# Board_v_03b.net
KiCad netlist of a schematic drawn in EAGLE
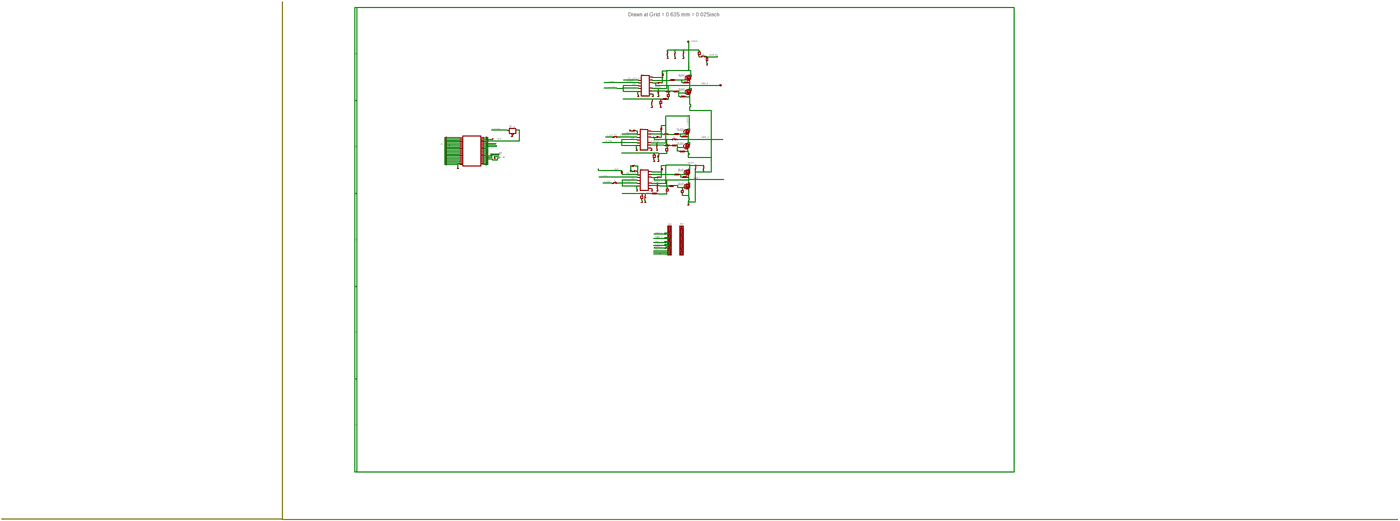
[diagram p0: schematic, sheet 1, overview]
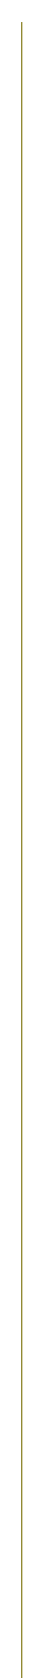
[diagram p1: schematic, sheet 1, part 1 of 7]
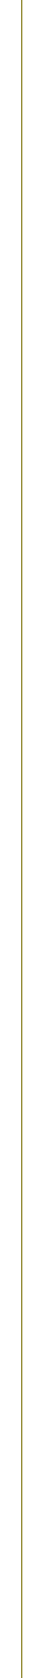
[diagram p2: schematic, sheet 1, part 2 of 7]
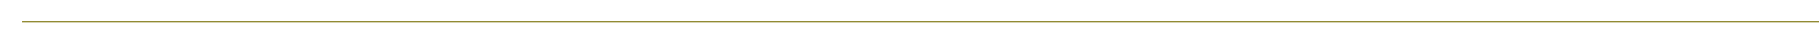
[diagram p3: schematic, sheet 1, part 3 of 7]
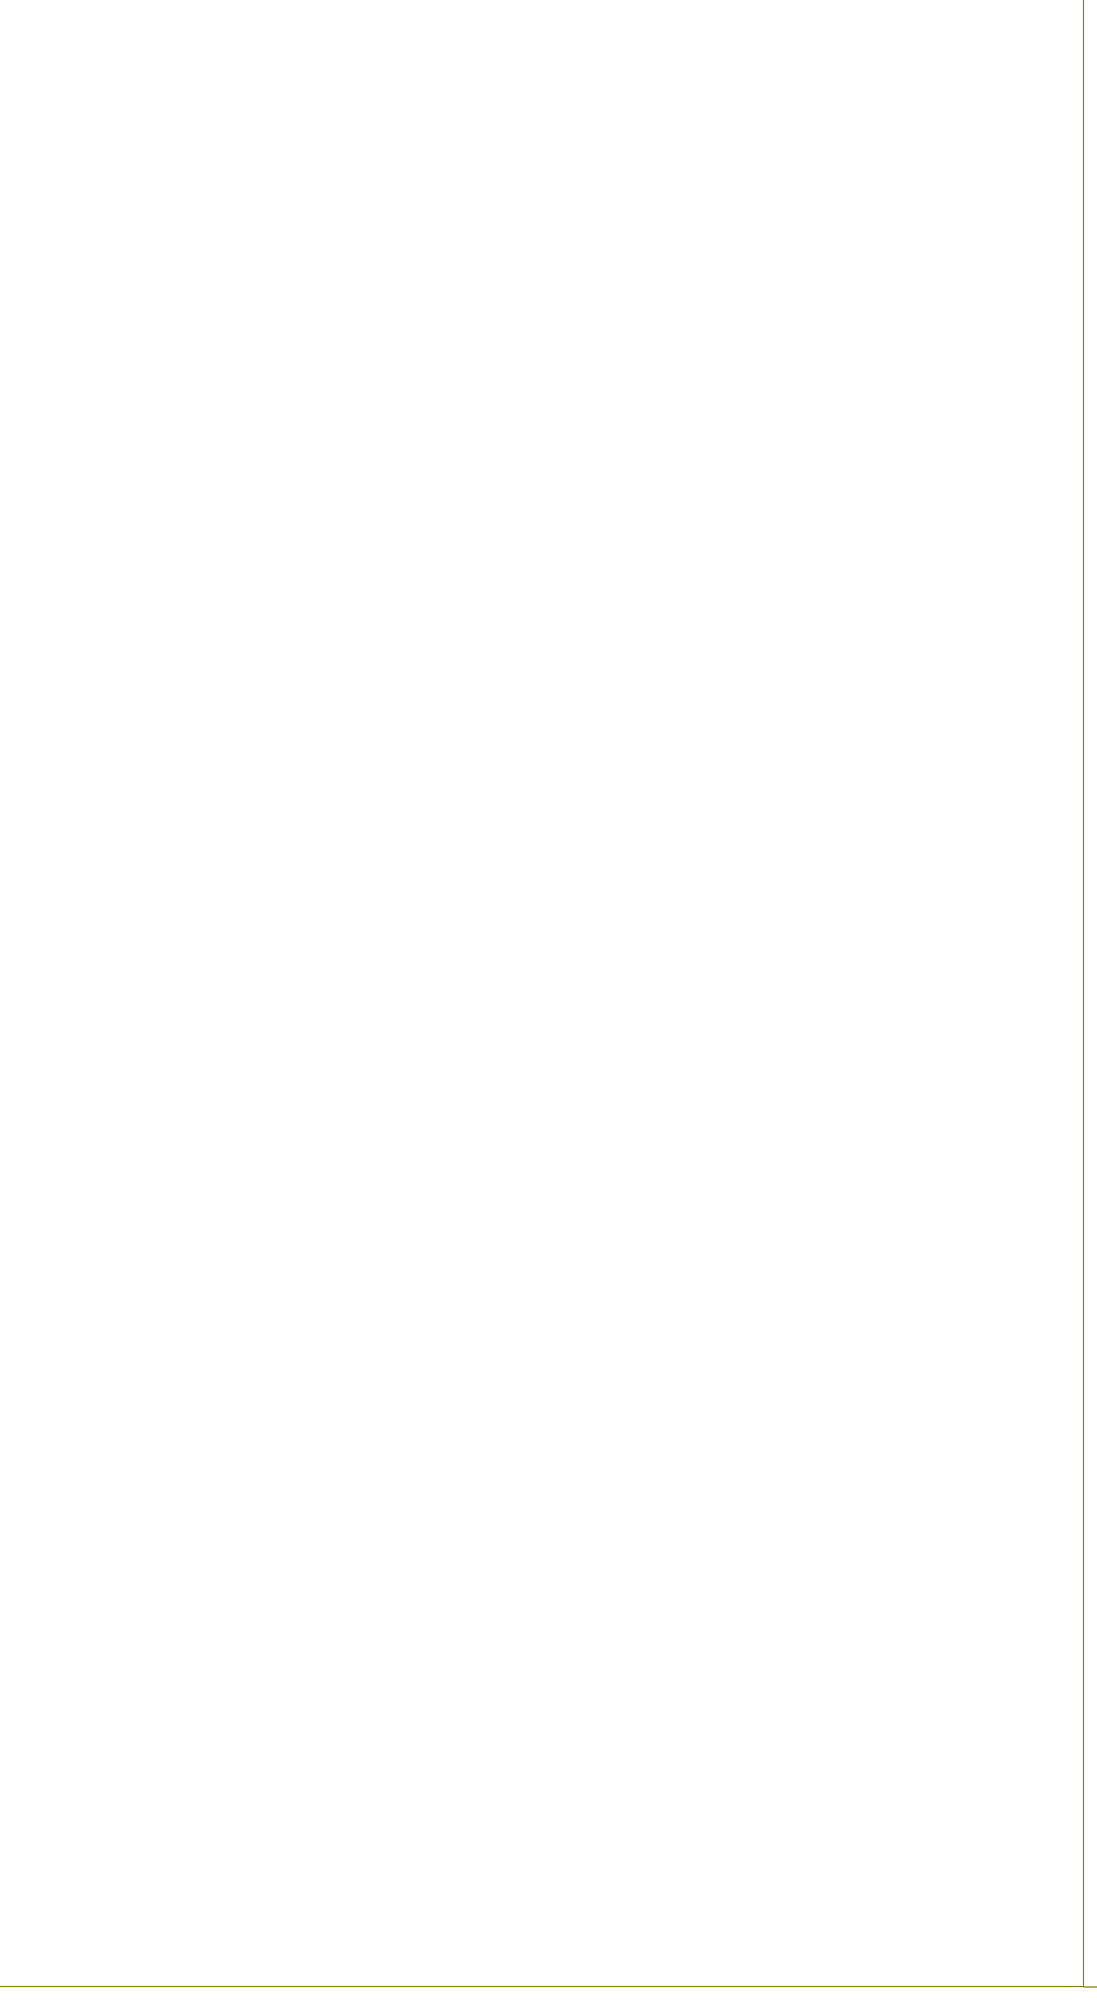
[diagram p4: schematic, sheet 1, part 4 of 7]
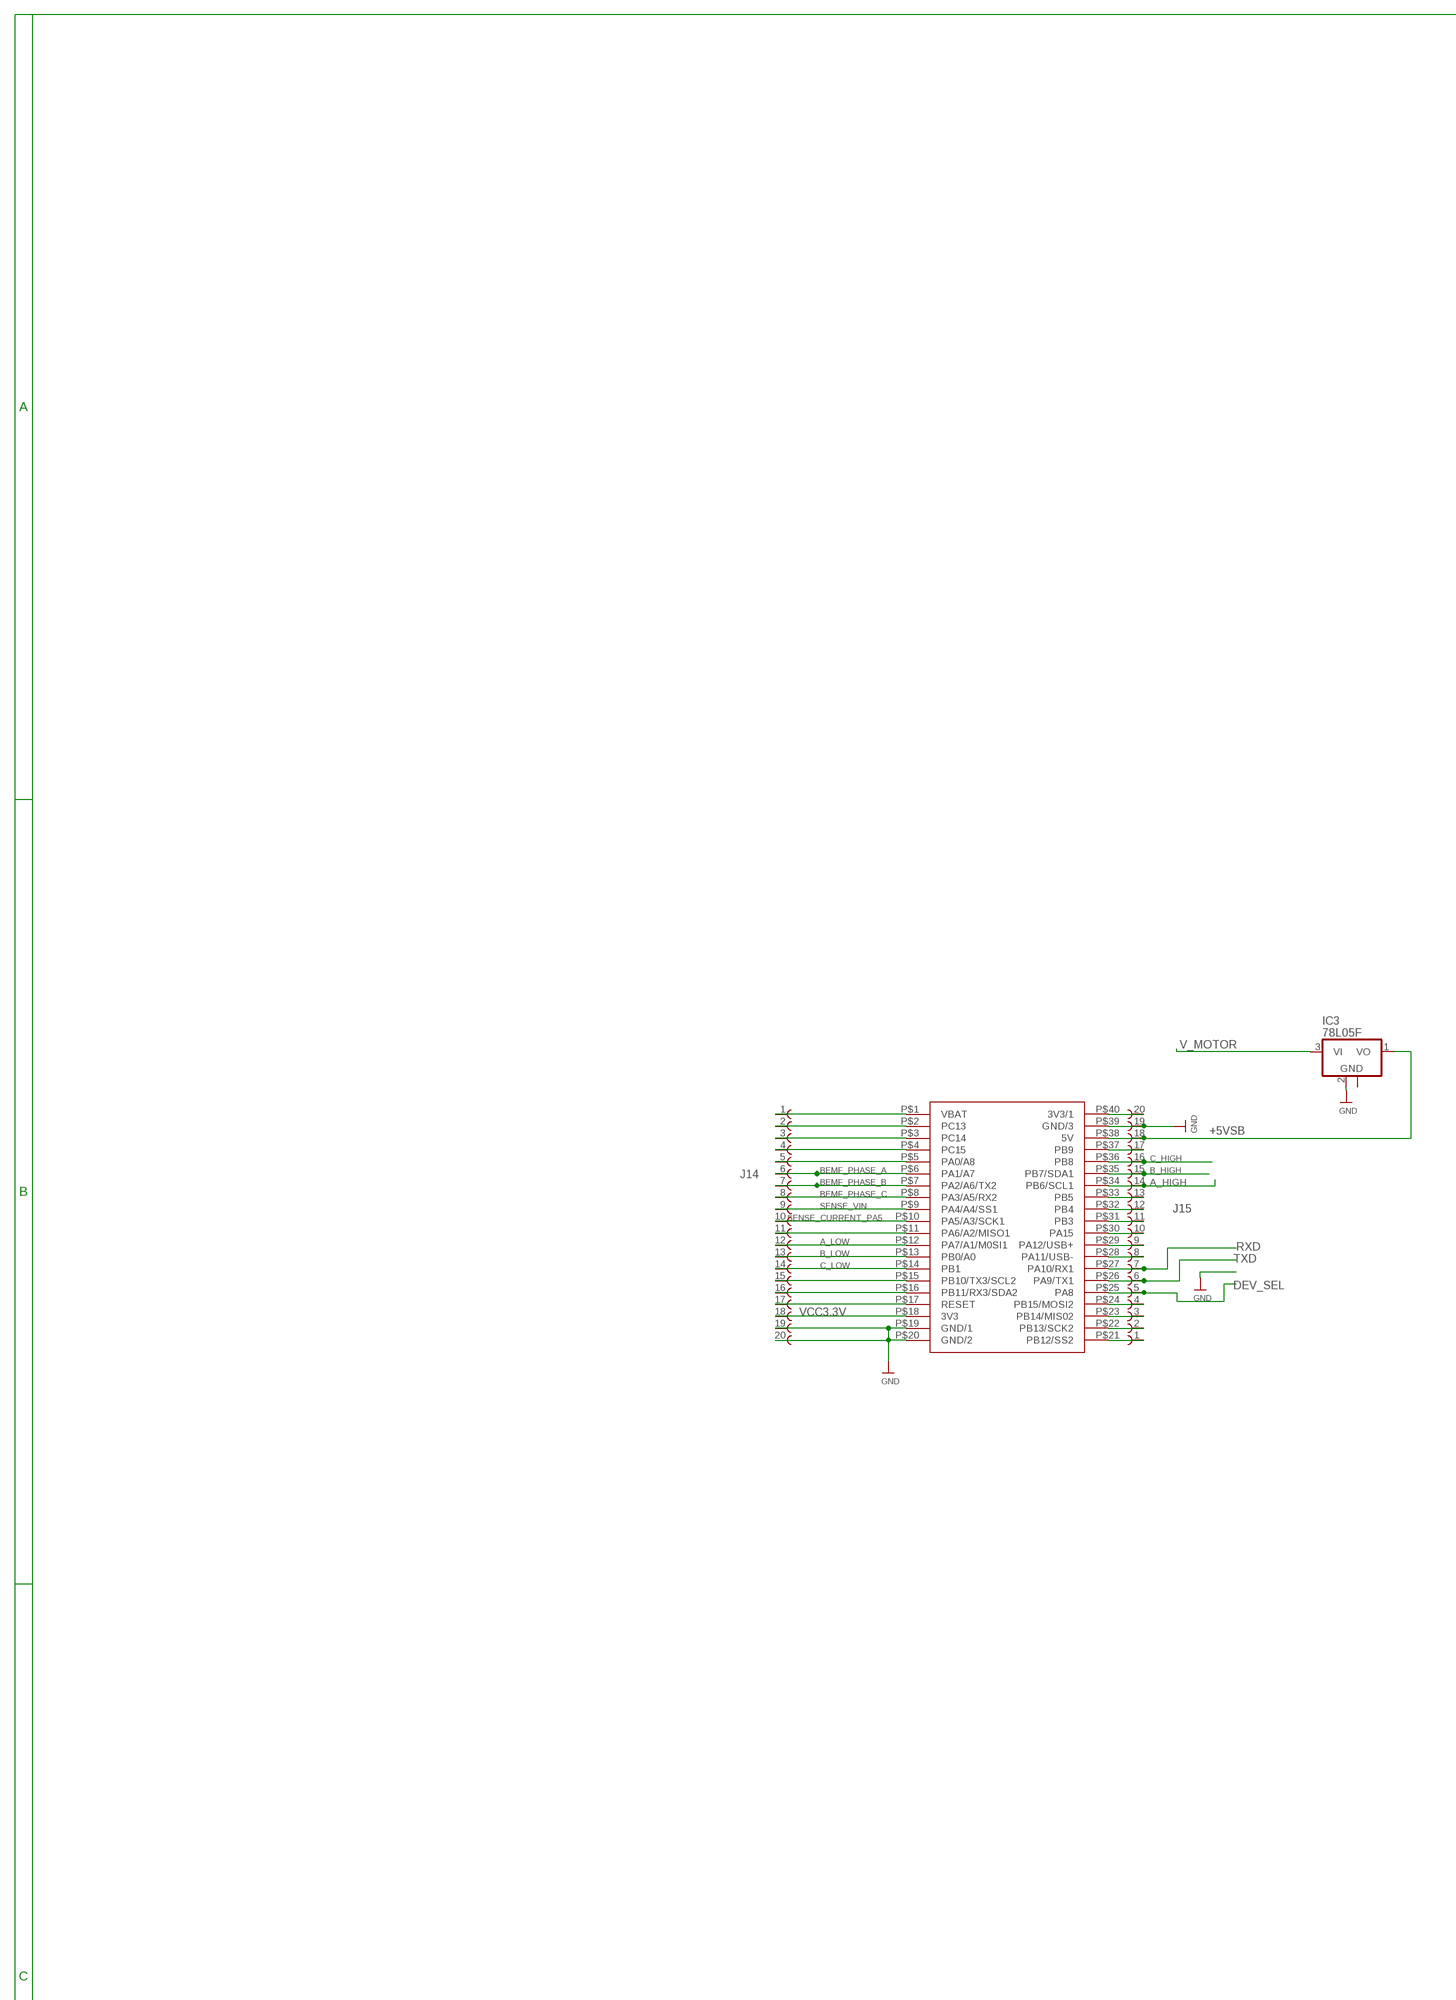
[diagram p5: schematic, sheet 1, part 5 of 7]
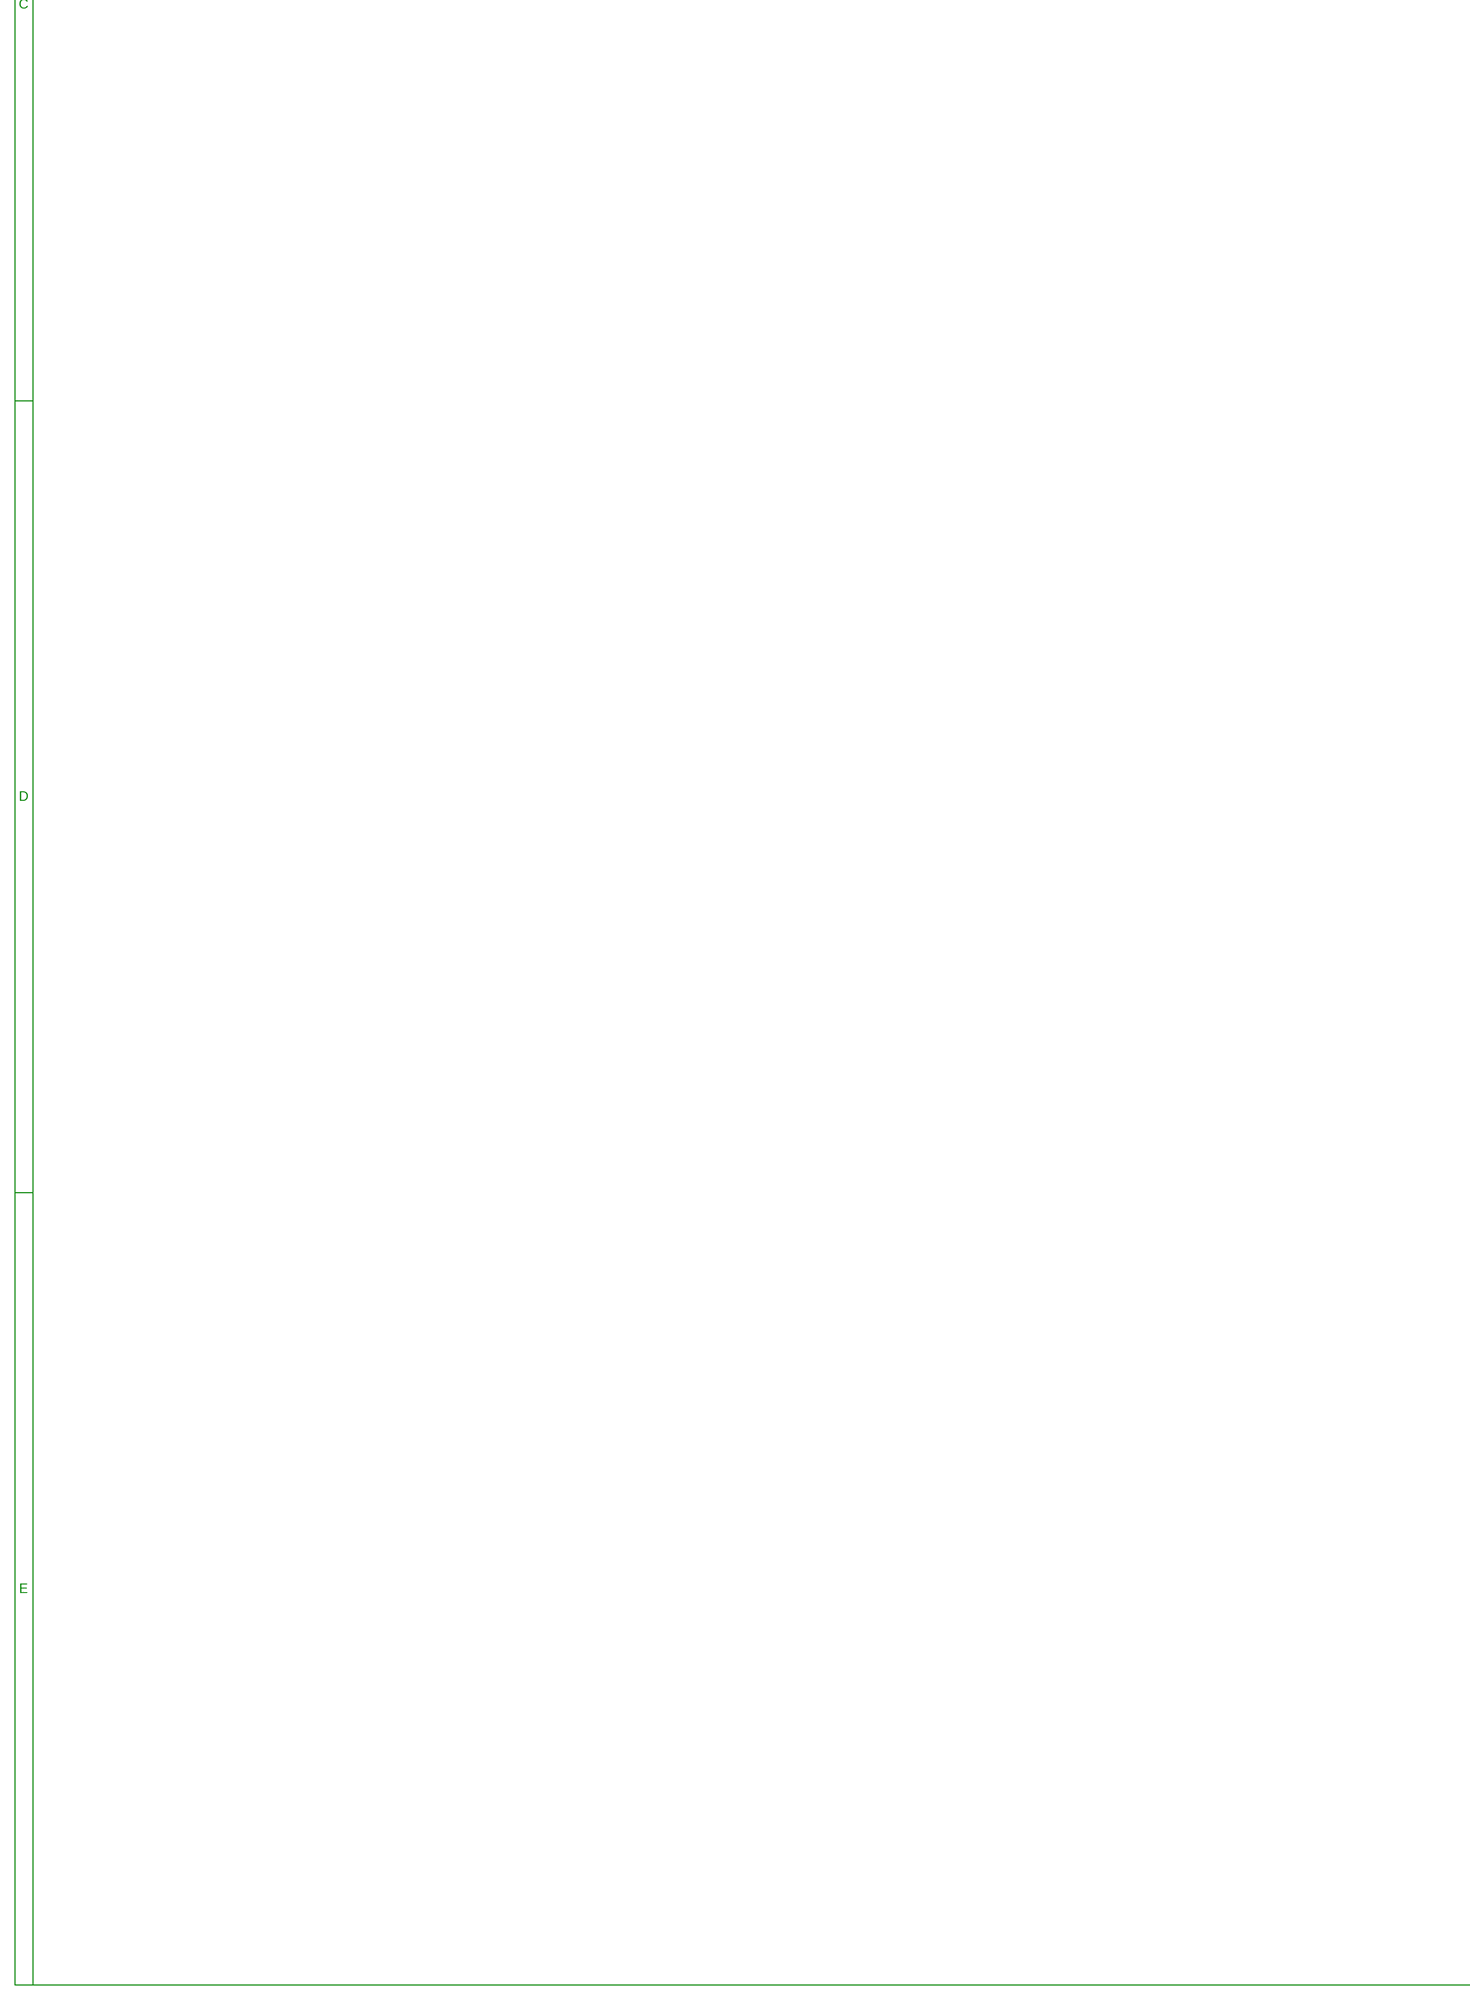
[diagram p6: schematic, sheet 1, part 6 of 7]
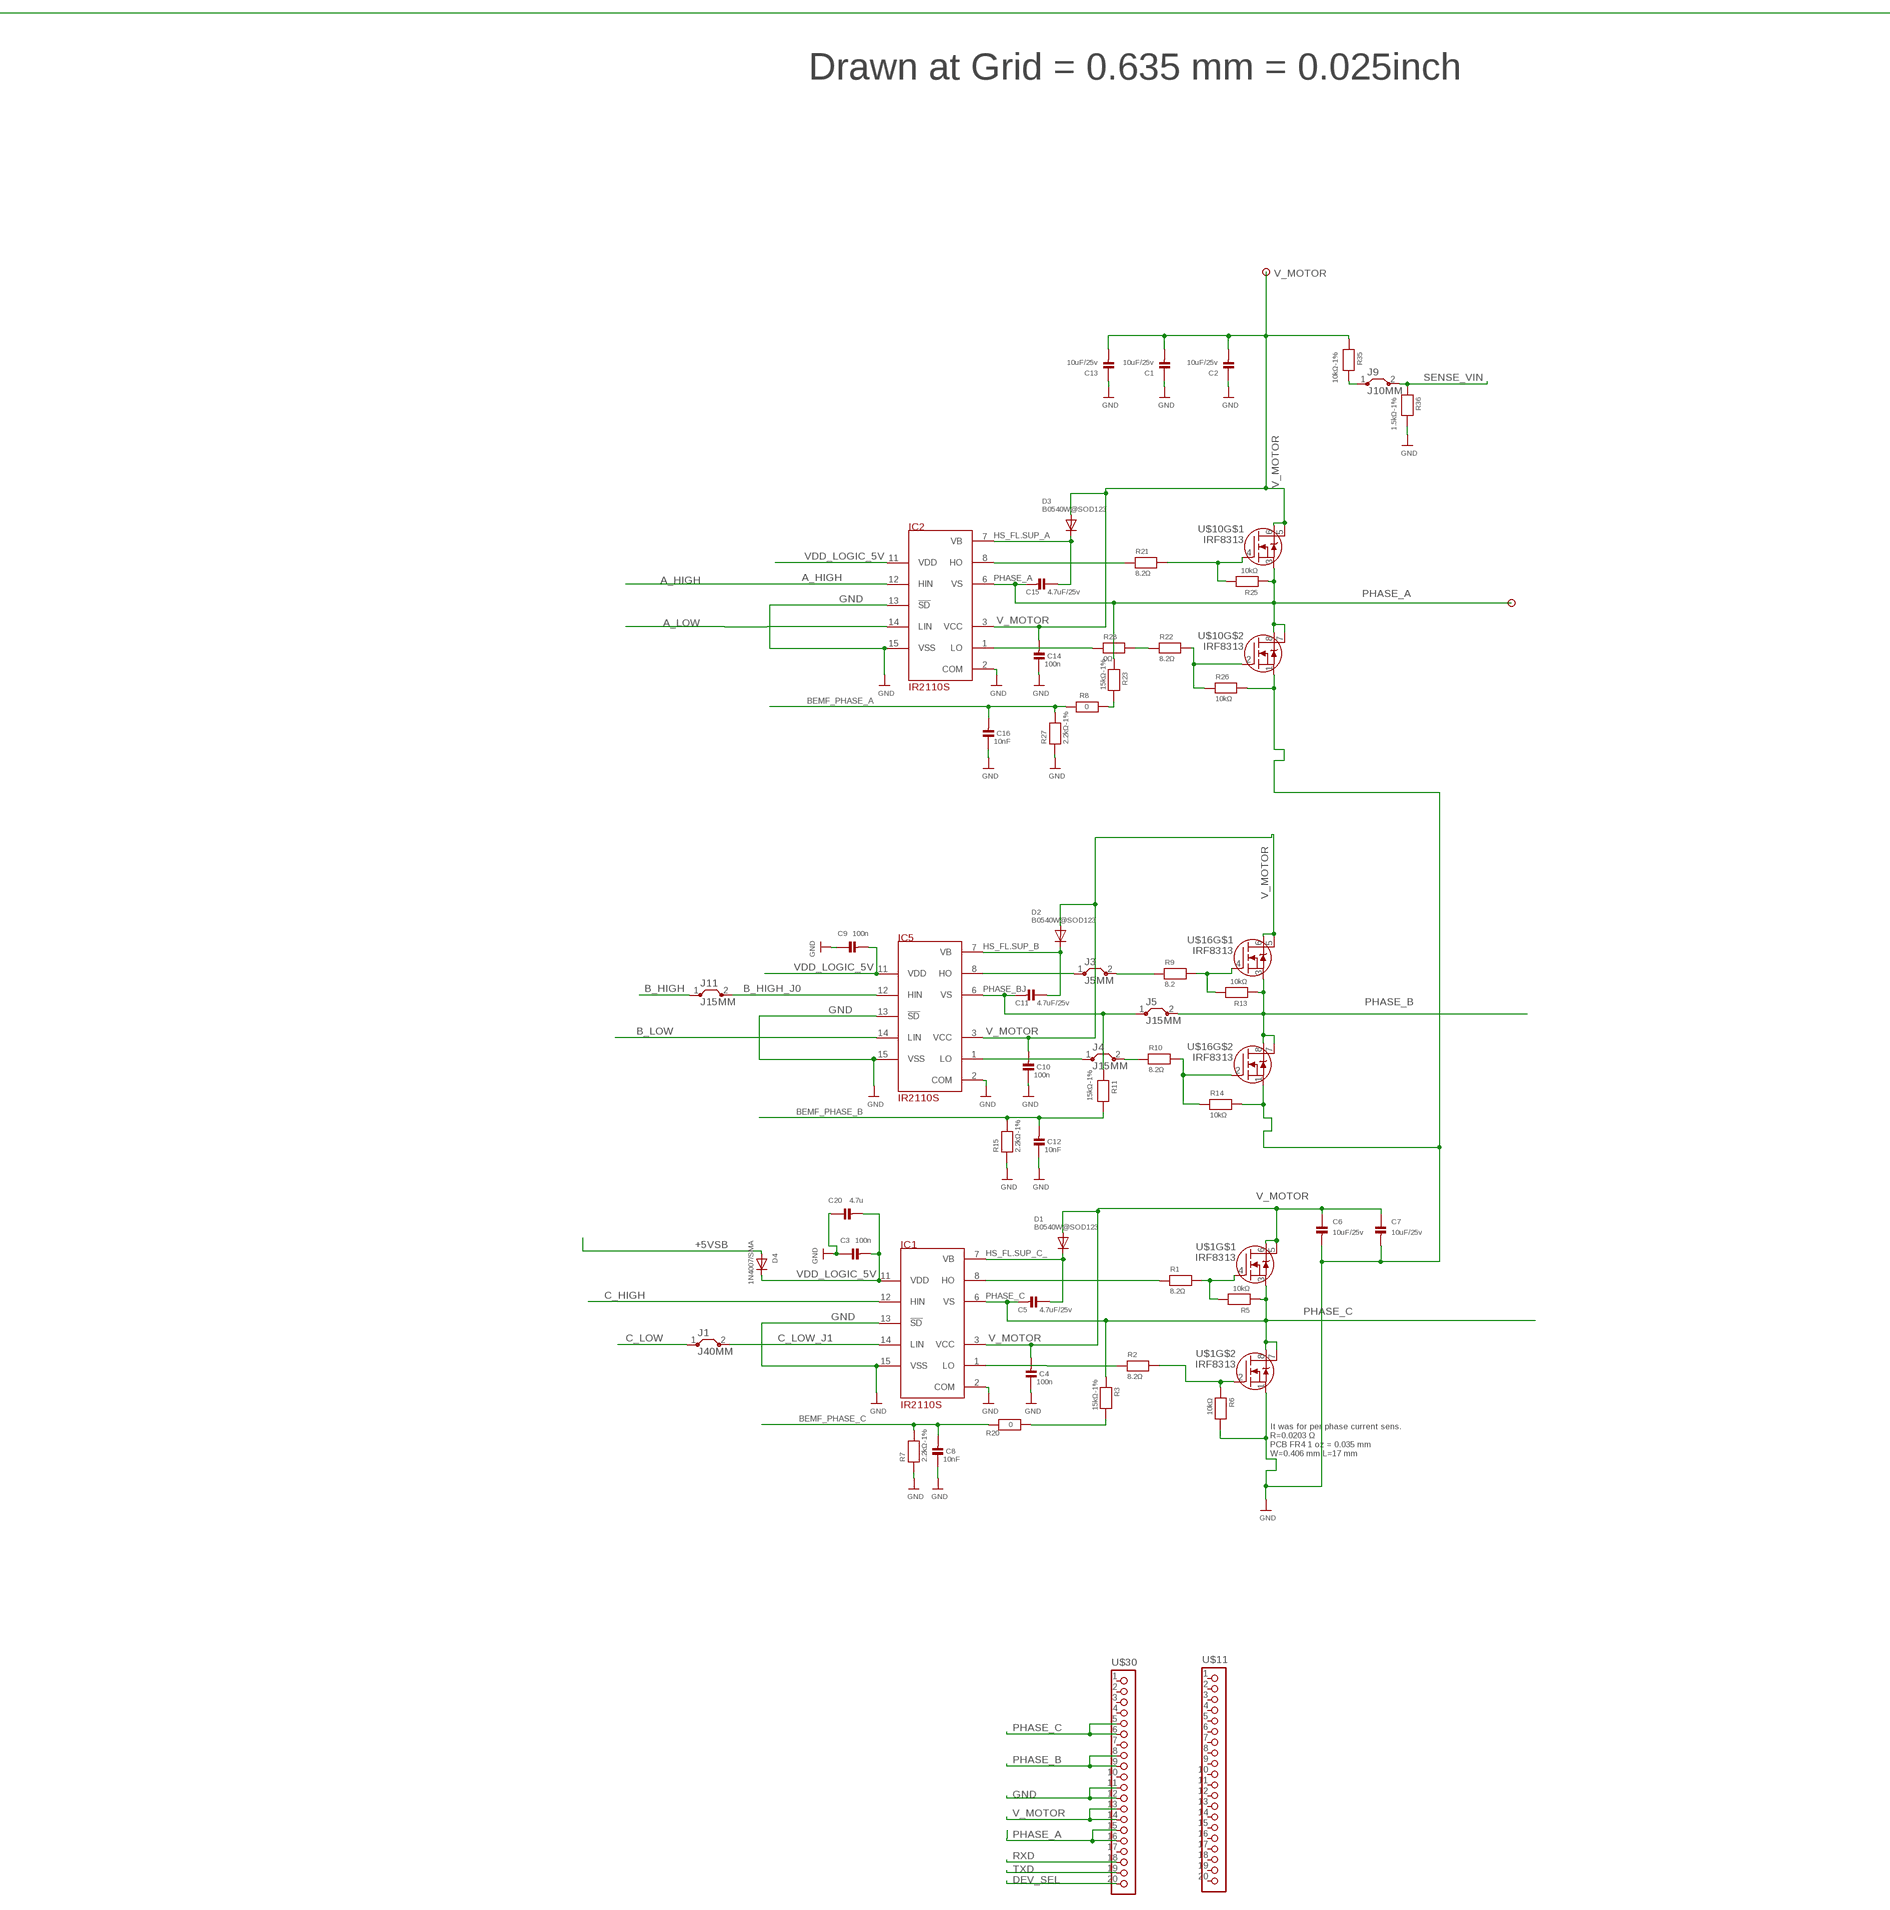
[diagram p7: schematic, sheet 1, part 7 of 7]

(export (version "E")
  (design (tool "Eeschema 10.0.6"))
  (components
    (comp (ref "C1")
      (value "10uF/25v")
      (footprint "eagle-import:_0805MP")
      (libsource (lib "eagle-import") (part "CAP_CERAMIC_0805MP"))
    )
    (comp (ref "C2")
      (value "10uF/25v")
      (footprint "eagle-import:_0805MP")
      (libsource (lib "eagle-import") (part "CAP_CERAMIC_0805MP"))
    )
    (comp (ref "C3")
      (value "100n")
      (footprint "eagle-import:_0805MP")
      (libsource (lib "eagle-import") (part "CAP_CERAMIC_0805MP"))
    )
    (comp (ref "C4")
      (value "100n")
      (footprint "eagle-import:_0603MP")
      (libsource (lib "eagle-import") (part "CAP_CERAMIC_0603MP"))
    )
    (comp (ref "C5")
      (value "4.7uF/25v")
      (footprint "eagle-import:_0805MP")
      (libsource (lib "eagle-import") (part "CAP_CERAMIC_0805MP"))
    )
    (comp (ref "C6")
      (value "10uF/25v")
      (footprint "eagle-import:_0805MP")
      (libsource (lib "eagle-import") (part "CAP_CERAMIC_0805MP"))
    )
    (comp (ref "C7")
      (value "10uF/25v")
      (footprint "eagle-import:_0805MP")
      (libsource (lib "eagle-import") (part "CAP_CERAMIC_0805MP"))
    )
    (comp (ref "C8")
      (value "10nF")
      (footprint "eagle-import:_0805MP")
      (libsource (lib "eagle-import") (part "CAP_CERAMIC_0805MP"))
    )
    (comp (ref "C9")
      (value "100n")
      (footprint "eagle-import:_0603MP")
      (libsource (lib "eagle-import") (part "CAP_CERAMIC_0603MP"))
    )
    (comp (ref "C10")
      (value "100n")
      (footprint "eagle-import:_0603MP")
      (libsource (lib "eagle-import") (part "CAP_CERAMIC_0603MP"))
    )
    (comp (ref "C11")
      (value "4.7uF/25v")
      (footprint "eagle-import:_0805MP")
      (libsource (lib "eagle-import") (part "CAP_CERAMIC_0805MP"))
    )
    (comp (ref "C12")
      (value "10nF")
      (footprint "eagle-import:_0805MP")
      (libsource (lib "eagle-import") (part "CAP_CERAMIC_0805MP"))
    )
    (comp (ref "C13")
      (value "10uF/25v")
      (footprint "eagle-import:_0805MP")
      (libsource (lib "eagle-import") (part "CAP_CERAMIC_0805MP"))
    )
    (comp (ref "C14")
      (value "100n")
      (footprint "eagle-import:_0603MP")
      (libsource (lib "eagle-import") (part "CAP_CERAMIC_0603MP"))
    )
    (comp (ref "C15")
      (value "4.7uF/25v")
      (footprint "eagle-import:_0805MP")
      (libsource (lib "eagle-import") (part "CAP_CERAMIC_0805MP"))
    )
    (comp (ref "C16")
      (value "10nF")
      (footprint "eagle-import:_0805MP")
      (libsource (lib "eagle-import") (part "CAP_CERAMIC_0805MP"))
    )
    (comp (ref "C20")
      (value "4.7u")
      (footprint "eagle-import:_0805MP")
      (libsource (lib "eagle-import") (part "CAP_CERAMIC_0805MP"))
    )
    (comp (ref "D1")
      (value "B0540W@SOD123")
      (footprint "eagle-import:SOD-123")
      (libsource (lib "eagle-import") (part "DIODESOD-123"))
    )
    (comp (ref "D2")
      (value "B0540W@SOD123")
      (footprint "eagle-import:SOD-123")
      (libsource (lib "eagle-import") (part "DIODESOD-123"))
    )
    (comp (ref "D3")
      (value "B0540W@SOD123")
      (footprint "eagle-import:SOD-123")
      (libsource (lib "eagle-import") (part "DIODESOD-123"))
    )
    (comp (ref "D4")
      (value "1N4007/SMA")
      (footprint "eagle-import:SMADIODE")
      (libsource (lib "eagle-import") (part "DIODESMA"))
    )
    (comp (ref "IC1")
      (value "IR2110S")
      (footprint "eagle-import:SO-16DW")
      (libsource (lib "eagle-import") (part "IR2110S"))
    )
    (comp (ref "IC2")
      (value "IR2110S")
      (footprint "eagle-import:SO-16DW")
      (libsource (lib "eagle-import") (part "IR2110S"))
    )
    (comp (ref "IC3")
      (value "78L05F")
      (footprint "eagle-import:SOT89")
      (libsource (lib "eagle-import") (part "78LF05"))
    )
    (comp (ref "IC5")
      (value "IR2110S")
      (footprint "eagle-import:SO-16DW")
      (libsource (lib "eagle-import") (part "IR2110S"))
    )
    (comp (ref "J1")
      (value "J40MM")
      (footprint "eagle-import:J40MM")
      (libsource (lib "eagle-import") (part "J40MM"))
    )
    (comp (ref "J3")
      (value "J5MM")
      (footprint "eagle-import:05")
      (libsource (lib "eagle-import") (part "jumper_J5MM"))
    )
    (comp (ref "J4")
      (value "J15MM")
      (footprint "eagle-import:15")
      (libsource (lib "eagle-import") (part "jumper_J15MM"))
    )
    (comp (ref "J5")
      (value "J15MM")
      (footprint "eagle-import:15")
      (libsource (lib "eagle-import") (part "jumper_J15MM"))
    )
    (comp (ref "J9")
      (value "J10MM")
      (footprint "eagle-import:10")
      (libsource (lib "eagle-import") (part "jumper_J10MM"))
    )
    (comp (ref "J11")
      (value "J15MM")
      (footprint "eagle-import:15")
      (libsource (lib "eagle-import") (part "jumper_J15MM"))
    )
    (comp (ref "J14")
      (value "61002013321")
      (footprint "eagle-import:CON-20PIN-SMD-MANUALLY-BENT-FROM-NON-SMD")
      (libsource (lib "eagle-import") (part "61002013321"))
    )
    (comp (ref "J15")
      (value "61002013321")
      (footprint "eagle-import:CON-20PIN-SMD-MANUALLY-BENT-FROM-NON-SMD")
      (libsource (lib "eagle-import") (part "61002013321"))
    )
    (comp (ref "PHASE_C")
      (value "PHASE_C")
      (footprint "eagle-import:PAD")
      (libsource (lib "eagle-import") (part "PAD"))
    )
    (comp (ref "R1")
      (value "8.2Ω")
      (footprint "eagle-import:_0805MP")
      (libsource (lib "eagle-import") (part "RESISTOR_0805MP"))
    )
    (comp (ref "R2")
      (value "8.2Ω")
      (footprint "eagle-import:_0805MP")
      (libsource (lib "eagle-import") (part "RESISTOR_0805MP"))
    )
    (comp (ref "R3")
      (value "15kΩ-1%")
      (footprint "eagle-import:_0805MP")
      (libsource (lib "eagle-import") (part "RESISTOR_0805MP"))
    )
    (comp (ref "R5")
      (value "10kΩ")
      (footprint "eagle-import:_0805MP")
      (libsource (lib "eagle-import") (part "RESISTOR_0805MP"))
    )
    (comp (ref "R6")
      (value "10kΩ")
      (footprint "eagle-import:_0805MP")
      (libsource (lib "eagle-import") (part "RESISTOR_0805MP"))
    )
    (comp (ref "R7")
      (value "2.2kΩ-1%")
      (footprint "eagle-import:_0805MP")
      (libsource (lib "eagle-import") (part "RESISTOR_0805MP"))
    )
    (comp (ref "R8")
      (value "0")
      (footprint "eagle-import:_0805MP")
      (libsource (lib "eagle-import") (part "RESISTOR_0805MP"))
    )
    (comp (ref "R9")
      (value "8.2")
      (footprint "eagle-import:_0805MP")
      (libsource (lib "eagle-import") (part "RESISTOR_0805MP"))
    )
    (comp (ref "R10")
      (value "8.2Ω")
      (footprint "eagle-import:_0805MP")
      (libsource (lib "eagle-import") (part "RESISTOR_0805MP"))
    )
    (comp (ref "R11")
      (value "15kΩ-1%")
      (footprint "eagle-import:_0805MP")
      (libsource (lib "eagle-import") (part "RESISTOR_0805MP"))
    )
    (comp (ref "R13")
      (value "10kΩ")
      (footprint "eagle-import:_0805MP")
      (libsource (lib "eagle-import") (part "RESISTOR_0805MP"))
    )
    (comp (ref "R14")
      (value "10kΩ")
      (footprint "eagle-import:_0805MP")
      (libsource (lib "eagle-import") (part "RESISTOR_0805MP"))
    )
    (comp (ref "R15")
      (value "2.2kΩ-1%")
      (footprint "eagle-import:_0805MP")
      (libsource (lib "eagle-import") (part "RESISTOR_0805MP"))
    )
    (comp (ref "R20")
      (value "0")
      (footprint "eagle-import:_0805MP")
      (libsource (lib "eagle-import") (part "RESISTOR_0805MP"))
    )
    (comp (ref "R21")
      (value "8.2Ω")
      (footprint "eagle-import:_0805MP")
      (libsource (lib "eagle-import") (part "RESISTOR_0805MP"))
    )
    (comp (ref "R22")
      (value "8.2Ω")
      (footprint "eagle-import:_0805MP")
      (libsource (lib "eagle-import") (part "RESISTOR_0805MP"))
    )
    (comp (ref "R23")
      (value "15kΩ-1%")
      (footprint "eagle-import:_0805MP")
      (libsource (lib "eagle-import") (part "RESISTOR_0805MP"))
    )
    (comp (ref "R25")
      (value "10kΩ")
      (footprint "eagle-import:_0805MP")
      (libsource (lib "eagle-import") (part "RESISTOR_0805MP"))
    )
    (comp (ref "R26")
      (value "10kΩ")
      (footprint "eagle-import:_0805MP")
      (libsource (lib "eagle-import") (part "RESISTOR_0805MP"))
    )
    (comp (ref "R27")
      (value "2.2kΩ-1%")
      (footprint "eagle-import:_0805MP")
      (libsource (lib "eagle-import") (part "RESISTOR_0805MP"))
    )
    (comp (ref "R28")
      (value "0Ω")
      (footprint "eagle-import:_0805MP")
      (libsource (lib "eagle-import") (part "RESISTOR_0805MP"))
    )
    (comp (ref "R35")
      (value "10kΩ-1%")
      (footprint "eagle-import:_0805MP")
      (libsource (lib "eagle-import") (part "RESISTOR_0805MP"))
    )
    (comp (ref "R36")
      (value "1.5kΩ-1%")
      (footprint "eagle-import:_0805MP")
      (libsource (lib "eagle-import") (part "RESISTOR_0805MP"))
    )
    (comp (ref "U$1")
      (value "IRF8313")
      (footprint "eagle-import:SO08")
      (libsource (lib "eagle-import") (part "IRF8313"))
    )
    (comp (ref "U$10")
      (value "IRF8313")
      (footprint "eagle-import:SO08")
      (libsource (lib "eagle-import") (part "IRF8313"))
    )
    (comp (ref "U$11")
      (value "CON_HEADER_1X20")
      (footprint "eagle-import:M1X20_SMD_2.54MM_0.1__LONGTRACKS")
      (libsource (lib "eagle-import") (part "CON_HEADER_1X20"))
    )
    (comp (ref "U$16")
      (value "IRF8313")
      (footprint "eagle-import:SO08")
      (libsource (lib "eagle-import") (part "IRF8313"))
    )
    (comp (ref "U$30")
      (value "CON_HEADER_1X20")
      (footprint "eagle-import:M1X20_SMD_2.54MM_0.1__LONGTRACKS")
      (libsource (lib "eagle-import") (part "CON_HEADER_1X20"))
    )
    (comp (ref "U$36")
      (value "BLUEPILL")
      (footprint "eagle-import:40-DIP-BLUE-PIL")
      (libsource (lib "eagle-import") (part "BLUEPILL"))
    )
    (comp (ref "V_MOTOR")
      (value "V_MOTOR")
      (footprint "eagle-import:PAD")
      (libsource (lib "eagle-import") (part "PAD"))
    )
  )
  (nets
    (net (code "1") (name "/+5VSB") (class "Default")
      (node (ref "D4") (pin "A") (pinfunction "A_A") (pintype "passive"))
      (node (ref "IC3") (pin "1") (pinfunction "VO_1") (pintype "passive"))
      (node (ref "J15") (pin "18") (pinfunction "18_18") (pintype "passive"))
      (node (ref "U$36") (pin "P$38") (pinfunction "5V_P$38") (pintype "bidirectional"))
    )
    (net (code "2") (name "/A_HIGH") (class "Default")
      (node (ref "IC2") (pin "12") (pinfunction "HIN_12") (pintype "input"))
      (node (ref "J15") (pin "14") (pinfunction "14_14") (pintype "passive"))
      (node (ref "U$36") (pin "P$34") (pinfunction "PB6/SCL1_P$34") (pintype "bidirectional"))
    )
    (net (code "3") (name "/A_LOW") (class "Default")
      (node (ref "IC2") (pin "14") (pinfunction "LIN_14") (pintype "input"))
      (node (ref "J14") (pin "12") (pinfunction "12_12") (pintype "passive"))
      (node (ref "U$36") (pin "P$12") (pinfunction "PA7/A1/M0SI1_P$12") (pintype "bidirectional"))
    )
    (net (code "4") (name "/BEMF_PHASE_A") (class "Default")
      (node (ref "C16") (pin "2") (pinfunction "P$2_2") (pintype "passive"))
      (node (ref "J14") (pin "6") (pinfunction "6_6") (pintype "passive"))
      (node (ref "R27") (pin "2") (pinfunction "2_2") (pintype "passive"))
      (node (ref "R8") (pin "1") (pinfunction "1_1") (pintype "passive"))
      (node (ref "U$36") (pin "P$6") (pinfunction "PA1/A7_P$6") (pintype "bidirectional"))
    )
    (net (code "5") (name "/BEMF_PHASE_B") (class "Default")
      (node (ref "C12") (pin "2") (pinfunction "P$2_2") (pintype "passive"))
      (node (ref "J14") (pin "7") (pinfunction "7_7") (pintype "passive"))
      (node (ref "R11") (pin "2") (pinfunction "2_2") (pintype "passive"))
      (node (ref "R15") (pin "2") (pinfunction "2_2") (pintype "passive"))
      (node (ref "U$36") (pin "P$7") (pinfunction "PA2/A6/TX2_P$7") (pintype "bidirectional"))
    )
    (net (code "6") (name "/BEMF_PHASE_C") (class "Default")
      (node (ref "C8") (pin "2") (pinfunction "P$2_2") (pintype "passive"))
      (node (ref "J14") (pin "8") (pinfunction "8_8") (pintype "passive"))
      (node (ref "R20") (pin "2") (pinfunction "2_2") (pintype "passive"))
      (node (ref "R7") (pin "2") (pinfunction "2_2") (pintype "passive"))
      (node (ref "U$36") (pin "P$8") (pinfunction "PA3/A5/RX2_P$8") (pintype "bidirectional"))
    )
    (net (code "7") (name "/B_HIGH") (class "Default")
      (node (ref "J11") (pin "1") (pinfunction "1_1") (pintype "passive"))
      (node (ref "J15") (pin "15") (pinfunction "15_15") (pintype "passive"))
      (node (ref "U$36") (pin "P$35") (pinfunction "PB7/SDA1_P$35") (pintype "bidirectional"))
    )
    (net (code "8") (name "/B_HIGH_J0") (class "Default")
      (node (ref "IC5") (pin "12") (pinfunction "HIN_12") (pintype "input"))
      (node (ref "J11") (pin "2") (pinfunction "2_2") (pintype "passive"))
    )
    (net (code "9") (name "/B_LOW") (class "Default")
      (node (ref "IC5") (pin "14") (pinfunction "LIN_14") (pintype "input"))
      (node (ref "J14") (pin "13") (pinfunction "13_13") (pintype "passive"))
      (node (ref "U$36") (pin "P$13") (pinfunction "PB0/A0_P$13") (pintype "bidirectional"))
    )
    (net (code "10") (name "/C_HIGH") (class "Default")
      (node (ref "IC1") (pin "12") (pinfunction "HIN_12") (pintype "input"))
      (node (ref "J15") (pin "16") (pinfunction "16_16") (pintype "passive"))
      (node (ref "U$36") (pin "P$36") (pinfunction "PB8_P$36") (pintype "bidirectional"))
    )
    (net (code "11") (name "/C_LOW") (class "Default")
      (node (ref "J1") (pin "1") (pinfunction "1_1") (pintype "passive"))
      (node (ref "J14") (pin "14") (pinfunction "14_14") (pintype "passive"))
      (node (ref "U$36") (pin "P$14") (pinfunction "PB1_P$14") (pintype "bidirectional"))
    )
    (net (code "12") (name "/C_LOW_J1") (class "Default")
      (node (ref "IC1") (pin "14") (pinfunction "LIN_14") (pintype "input"))
      (node (ref "J1") (pin "2") (pinfunction "2_2") (pintype "passive"))
    )
    (net (code "13") (name "/DEV_SEL") (class "Default")
      (node (ref "J15") (pin "5") (pinfunction "5_5") (pintype "passive"))
      (node (ref "U$30") (pin "20") (pinfunction "20_20") (pintype "passive"))
      (node (ref "U$36") (pin "P$25") (pinfunction "PA8_P$25") (pintype "bidirectional"))
    )
    (net (code "14") (name "/HS_FL.SUP_A") (class "Default")
      (node (ref "C15") (pin "1") (pinfunction "P$1_1") (pintype "passive"))
      (node (ref "D3") (pin "C") (pinfunction "C_C") (pintype "passive"))
      (node (ref "IC2") (pin "7") (pinfunction "VB_7") (pintype "power_in"))
    )
    (net (code "15") (name "/HS_FL.SUP_B") (class "Default")
      (node (ref "C11") (pin "1") (pinfunction "P$1_1") (pintype "passive"))
      (node (ref "D2") (pin "C") (pinfunction "C_C") (pintype "passive"))
      (node (ref "IC5") (pin "7") (pinfunction "VB_7") (pintype "power_in"))
    )
    (net (code "16") (name "/HS_FL.SUP_C_") (class "Default")
      (node (ref "C5") (pin "1") (pinfunction "P$1_1") (pintype "passive"))
      (node (ref "D1") (pin "C") (pinfunction "C_C") (pintype "passive"))
      (node (ref "IC1") (pin "7") (pinfunction "VB_7") (pintype "power_in"))
    )
    (net (code "17") (name "/PHASE_A") (class "Default")
      (node (ref "C15") (pin "2") (pinfunction "P$2_2") (pintype "passive"))
      (node (ref "IC2") (pin "6") (pinfunction "VS_6") (pintype "power_in"))
      (node (ref "PHASE_C") (pin "1") (pinfunction "1_1") (pintype "bidirectional"))
      (node (ref "R23") (pin "1") (pinfunction "1_1") (pintype "passive"))
      (node (ref "R25") (pin "1") (pinfunction "1_1") (pintype "passive"))
      (node (ref "U$10") (pin "3") (pinfunction "S_3") (pintype "bidirectional"))
      (node (ref "U$10") (pin "7") (pinfunction "D_7") (pintype "bidirectional"))
      (node (ref "U$10") (pin "8") (pinfunction "D_8") (pintype "bidirectional"))
      (node (ref "U$30") (pin "15") (pinfunction "15_15") (pintype "passive"))
      (node (ref "U$30") (pin "16") (pinfunction "16_16") (pintype "passive"))
    )
    (net (code "18") (name "/PHASE_B") (class "Default")
      (node (ref "J5") (pin "2") (pinfunction "2_2") (pintype "passive"))
      (node (ref "R13") (pin "1") (pinfunction "1_1") (pintype "passive"))
      (node (ref "U$16") (pin "3") (pinfunction "S_3") (pintype "bidirectional"))
      (node (ref "U$16") (pin "7") (pinfunction "D_7") (pintype "bidirectional"))
      (node (ref "U$16") (pin "8") (pinfunction "D_8") (pintype "bidirectional"))
      (node (ref "U$30") (pin "8") (pinfunction "8_8") (pintype "passive"))
      (node (ref "U$30") (pin "9") (pinfunction "9_9") (pintype "passive"))
    )
    (net (code "19") (name "/PHASE_BJ") (class "Default")
      (node (ref "C11") (pin "2") (pinfunction "P$2_2") (pintype "passive"))
      (node (ref "IC5") (pin "6") (pinfunction "VS_6") (pintype "power_in"))
      (node (ref "J5") (pin "1") (pinfunction "1_1") (pintype "passive"))
      (node (ref "R11") (pin "1") (pinfunction "1_1") (pintype "passive"))
    )
    (net (code "20") (name "/PHASE_C") (class "Default")
      (node (ref "C5") (pin "2") (pinfunction "P$2_2") (pintype "passive"))
      (node (ref "IC1") (pin "6") (pinfunction "VS_6") (pintype "power_in"))
      (node (ref "R3") (pin "1") (pinfunction "1_1") (pintype "passive"))
      (node (ref "R5") (pin "1") (pinfunction "1_1") (pintype "passive"))
      (node (ref "U$1") (pin "3") (pinfunction "S_3") (pintype "bidirectional"))
      (node (ref "U$1") (pin "7") (pinfunction "D_7") (pintype "bidirectional"))
      (node (ref "U$1") (pin "8") (pinfunction "D_8") (pintype "bidirectional"))
      (node (ref "U$30") (pin "5") (pinfunction "5_5") (pintype "passive"))
      (node (ref "U$30") (pin "6") (pinfunction "6_6") (pintype "passive"))
    )
    (net (code "21") (name "/RXD") (class "Default")
      (node (ref "J15") (pin "7") (pinfunction "7_7") (pintype "passive"))
      (node (ref "U$30") (pin "18") (pinfunction "18_18") (pintype "passive"))
      (node (ref "U$36") (pin "P$27") (pinfunction "PA10/RX1_P$27") (pintype "bidirectional"))
    )
    (net (code "22") (name "/SENSE_CURRENT_PA5") (class "Default")
      (node (ref "J14") (pin "10") (pinfunction "10_10") (pintype "passive"))
      (node (ref "U$36") (pin "P$10") (pinfunction "PA5/A3/SCK1_P$10") (pintype "bidirectional"))
    )
    (net (code "23") (name "/SENSE_VIN") (class "Default")
      (node (ref "J14") (pin "9") (pinfunction "9_9") (pintype "passive"))
      (node (ref "J9") (pin "2") (pinfunction "2_2") (pintype "passive"))
      (node (ref "R36") (pin "1") (pinfunction "1_1") (pintype "passive"))
      (node (ref "U$36") (pin "P$9") (pinfunction "PA4/A4/SS1_P$9") (pintype "bidirectional"))
    )
    (net (code "24") (name "/TXD") (class "Default")
      (node (ref "J15") (pin "6") (pinfunction "6_6") (pintype "passive"))
      (node (ref "U$30") (pin "19") (pinfunction "19_19") (pintype "passive"))
      (node (ref "U$36") (pin "P$26") (pinfunction "PA9/TX1_P$26") (pintype "bidirectional"))
    )
    (net (code "25") (name "/VCC3.3V") (class "Default")
      (node (ref "J14") (pin "18") (pinfunction "18_18") (pintype "passive"))
      (node (ref "U$36") (pin "P$18") (pinfunction "3V3_P$18") (pintype "bidirectional"))
    )
    (net (code "26") (name "/VDD_LOGIC_5V") (class "Default")
      (node (ref "C20") (pin "2") (pinfunction "P$2_2") (pintype "passive"))
      (node (ref "C3") (pin "2") (pinfunction "P$2_2") (pintype "passive"))
      (node (ref "C9") (pin "2") (pinfunction "P$2_2") (pintype "passive"))
      (node (ref "D4") (pin "C") (pinfunction "C_C") (pintype "passive"))
      (node (ref "IC1") (pin "11") (pinfunction "VDD_11") (pintype "power_in"))
      (node (ref "IC2") (pin "11") (pinfunction "VDD_11") (pintype "power_in"))
      (node (ref "IC5") (pin "11") (pinfunction "VDD_11") (pintype "power_in"))
    )
    (net (code "27") (name "/V_MOTOR") (class "Default")
      (node (ref "C1") (pin "2") (pinfunction "P$2_2") (pintype "passive"))
      (node (ref "C10") (pin "2") (pinfunction "P$2_2") (pintype "passive"))
      (node (ref "C13") (pin "2") (pinfunction "P$2_2") (pintype "passive"))
      (node (ref "C14") (pin "2") (pinfunction "P$2_2") (pintype "passive"))
      (node (ref "C2") (pin "2") (pinfunction "P$2_2") (pintype "passive"))
      (node (ref "C4") (pin "2") (pinfunction "P$2_2") (pintype "passive"))
      (node (ref "C6") (pin "1") (pinfunction "P$1_1") (pintype "passive"))
      (node (ref "C7") (pin "1") (pinfunction "P$1_1") (pintype "passive"))
      (node (ref "D1") (pin "A") (pinfunction "A_A") (pintype "passive"))
      (node (ref "D2") (pin "A") (pinfunction "A_A") (pintype "passive"))
      (node (ref "D3") (pin "A") (pinfunction "A_A") (pintype "passive"))
      (node (ref "IC1") (pin "3") (pinfunction "VCC_3") (pintype "power_in"))
      (node (ref "IC2") (pin "3") (pinfunction "VCC_3") (pintype "power_in"))
      (node (ref "IC3") (pin "3") (pinfunction "VI_3") (pintype "input"))
      (node (ref "IC5") (pin "3") (pinfunction "VCC_3") (pintype "power_in"))
      (node (ref "R35") (pin "1") (pinfunction "1_1") (pintype "passive"))
      (node (ref "U$1") (pin "5") (pinfunction "D_5") (pintype "bidirectional"))
      (node (ref "U$1") (pin "6") (pinfunction "D_6") (pintype "bidirectional"))
      (node (ref "U$10") (pin "5") (pinfunction "D_5") (pintype "bidirectional"))
      (node (ref "U$10") (pin "6") (pinfunction "D_6") (pintype "bidirectional"))
      (node (ref "U$16") (pin "5") (pinfunction "D_5") (pintype "bidirectional"))
      (node (ref "U$16") (pin "6") (pinfunction "D_6") (pintype "bidirectional"))
      (node (ref "U$30") (pin "13") (pinfunction "13_13") (pintype "passive"))
      (node (ref "U$30") (pin "14") (pinfunction "14_14") (pintype "passive"))
      (node (ref "V_MOTOR") (pin "1") (pinfunction "1_1") (pintype "bidirectional"))
    )
    (net (code "28") (name "GND") (class "Default")
      (node (ref "C1") (pin "1") (pinfunction "P$1_1") (pintype "passive"))
      (node (ref "C10") (pin "1") (pinfunction "P$1_1") (pintype "passive"))
      (node (ref "C12") (pin "1") (pinfunction "P$1_1") (pintype "passive"))
      (node (ref "C13") (pin "1") (pinfunction "P$1_1") (pintype "passive"))
      (node (ref "C14") (pin "1") (pinfunction "P$1_1") (pintype "passive"))
      (node (ref "C16") (pin "1") (pinfunction "P$1_1") (pintype "passive"))
      (node (ref "C2") (pin "1") (pinfunction "P$1_1") (pintype "passive"))
      (node (ref "C20") (pin "1") (pinfunction "P$1_1") (pintype "passive"))
      (node (ref "C3") (pin "1") (pinfunction "P$1_1") (pintype "passive"))
      (node (ref "C4") (pin "1") (pinfunction "P$1_1") (pintype "passive"))
      (node (ref "C6") (pin "2") (pinfunction "P$2_2") (pintype "passive"))
      (node (ref "C7") (pin "2") (pinfunction "P$2_2") (pintype "passive"))
      (node (ref "C8") (pin "1") (pinfunction "P$1_1") (pintype "passive"))
      (node (ref "C9") (pin "1") (pinfunction "P$1_1") (pintype "passive"))
      (node (ref "IC1") (pin "13") (pinfunction "~{SD}_13") (pintype "input"))
      (node (ref "IC1") (pin "15") (pinfunction "VSS_15") (pintype "power_in"))
      (node (ref "IC1") (pin "2") (pinfunction "COM_2") (pintype "power_in"))
      (node (ref "IC2") (pin "13") (pinfunction "~{SD}_13") (pintype "input"))
      (node (ref "IC2") (pin "15") (pinfunction "VSS_15") (pintype "power_in"))
      (node (ref "IC2") (pin "2") (pinfunction "COM_2") (pintype "power_in"))
      (node (ref "IC3") (pin "2") (pinfunction "GND_2") (pintype "passive"))
      (node (ref "IC5") (pin "13") (pinfunction "~{SD}_13") (pintype "input"))
      (node (ref "IC5") (pin "15") (pinfunction "VSS_15") (pintype "power_in"))
      (node (ref "IC5") (pin "2") (pinfunction "COM_2") (pintype "power_in"))
      (node (ref "J14") (pin "19") (pinfunction "19_19") (pintype "passive"))
      (node (ref "J14") (pin "20") (pinfunction "20_20") (pintype "passive"))
      (node (ref "J15") (pin "19") (pinfunction "19_19") (pintype "passive"))
      (node (ref "R14") (pin "2") (pinfunction "2_2") (pintype "passive"))
      (node (ref "R15") (pin "1") (pinfunction "1_1") (pintype "passive"))
      (node (ref "R26") (pin "2") (pinfunction "2_2") (pintype "passive"))
      (node (ref "R27") (pin "1") (pinfunction "1_1") (pintype "passive"))
      (node (ref "R36") (pin "2") (pinfunction "2_2") (pintype "passive"))
      (node (ref "R6") (pin "2") (pinfunction "2_2") (pintype "passive"))
      (node (ref "R7") (pin "1") (pinfunction "1_1") (pintype "passive"))
      (node (ref "U$1") (pin "1") (pinfunction "S_1") (pintype "bidirectional"))
      (node (ref "U$10") (pin "1") (pinfunction "S_1") (pintype "bidirectional"))
      (node (ref "U$16") (pin "1") (pinfunction "S_1") (pintype "bidirectional"))
      (node (ref "U$30") (pin "11") (pinfunction "11_11") (pintype "passive"))
      (node (ref "U$30") (pin "12") (pinfunction "12_12") (pintype "passive"))
      (node (ref "U$36") (pin "P$19") (pinfunction "GND/1_P$19") (pintype "bidirectional"))
      (node (ref "U$36") (pin "P$20") (pinfunction "GND/2_P$20") (pintype "bidirectional"))
      (node (ref "U$36") (pin "P$39") (pinfunction "GND/3_P$39") (pintype "bidirectional"))
    )
    (net (code "29") (name "Net-(IC1-HO)") (class "Default")
      (node (ref "IC1") (pin "8") (pinfunction "HO_8") (pintype "output"))
      (node (ref "R1") (pin "1") (pinfunction "1_1") (pintype "passive"))
    )
    (net (code "30") (name "Net-(IC1-LO)") (class "Default")
      (node (ref "IC1") (pin "1") (pinfunction "LO_1") (pintype "output"))
      (node (ref "R2") (pin "1") (pinfunction "1_1") (pintype "passive"))
    )
    (net (code "31") (name "Net-(IC2-HO)") (class "Default")
      (node (ref "IC2") (pin "8") (pinfunction "HO_8") (pintype "output"))
      (node (ref "R21") (pin "1") (pinfunction "1_1") (pintype "passive"))
    )
    (net (code "32") (name "Net-(IC2-LO)") (class "Default")
      (node (ref "IC2") (pin "1") (pinfunction "LO_1") (pintype "output"))
      (node (ref "R28") (pin "1") (pinfunction "1_1") (pintype "passive"))
    )
    (net (code "33") (name "Net-(IC5-HO)") (class "Default")
      (node (ref "IC5") (pin "8") (pinfunction "HO_8") (pintype "output"))
      (node (ref "J3") (pin "1") (pinfunction "1_1") (pintype "passive"))
    )
    (net (code "34") (name "Net-(IC5-LO)") (class "Default")
      (node (ref "IC5") (pin "1") (pinfunction "LO_1") (pintype "output"))
      (node (ref "J4") (pin "1") (pinfunction "1_1") (pintype "passive"))
    )
    (net (code "35") (name "Net-(J3-Pad2)") (class "Default")
      (node (ref "J3") (pin "2") (pinfunction "2_2") (pintype "passive"))
      (node (ref "R9") (pin "1") (pinfunction "1_1") (pintype "passive"))
    )
    (net (code "36") (name "Net-(J4-Pad2)") (class "Default")
      (node (ref "J4") (pin "2") (pinfunction "2_2") (pintype "passive"))
      (node (ref "R10") (pin "1") (pinfunction "1_1") (pintype "passive"))
    )
    (net (code "37") (name "Net-(J9-Pad1)") (class "Default")
      (node (ref "J9") (pin "1") (pinfunction "1_1") (pintype "passive"))
      (node (ref "R35") (pin "2") (pinfunction "2_2") (pintype "passive"))
    )
    (net (code "38") (name "Net-(R20-Pad1)") (class "Default")
      (node (ref "R20") (pin "1") (pinfunction "1_1") (pintype "passive"))
      (node (ref "R3") (pin "2") (pinfunction "2_2") (pintype "passive"))
    )
    (net (code "39") (name "Net-(R22-Pad1)") (class "Default")
      (node (ref "R22") (pin "1") (pinfunction "1_1") (pintype "passive"))
      (node (ref "R28") (pin "2") (pinfunction "2_2") (pintype "passive"))
    )
    (net (code "40") (name "Net-(R23-Pad2)") (class "Default")
      (node (ref "R23") (pin "2") (pinfunction "2_2") (pintype "passive"))
      (node (ref "R8") (pin "2") (pinfunction "2_2") (pintype "passive"))
    )
    (net (code "41") (name "Net-(U$1A-G)") (class "Default")
      (node (ref "R1") (pin "2") (pinfunction "2_2") (pintype "passive"))
      (node (ref "R5") (pin "2") (pinfunction "2_2") (pintype "passive"))
      (node (ref "U$1") (pin "4") (pinfunction "G_4") (pintype "input"))
    )
    (net (code "42") (name "Net-(U$1B-G)") (class "Default")
      (node (ref "R2") (pin "2") (pinfunction "2_2") (pintype "passive"))
      (node (ref "R6") (pin "1") (pinfunction "1_1") (pintype "passive"))
      (node (ref "U$1") (pin "2") (pinfunction "G_2") (pintype "input"))
    )
    (net (code "43") (name "Net-(U$10A-G)") (class "Default")
      (node (ref "R21") (pin "2") (pinfunction "2_2") (pintype "passive"))
      (node (ref "R25") (pin "2") (pinfunction "2_2") (pintype "passive"))
      (node (ref "U$10") (pin "4") (pinfunction "G_4") (pintype "input"))
    )
    (net (code "44") (name "Net-(U$10B-G)") (class "Default")
      (node (ref "R22") (pin "2") (pinfunction "2_2") (pintype "passive"))
      (node (ref "R26") (pin "1") (pinfunction "1_1") (pintype "passive"))
      (node (ref "U$10") (pin "2") (pinfunction "G_2") (pintype "input"))
    )
    (net (code "45") (name "Net-(U$16A-G)") (class "Default")
      (node (ref "R13") (pin "2") (pinfunction "2_2") (pintype "passive"))
      (node (ref "R9") (pin "2") (pinfunction "2_2") (pintype "passive"))
      (node (ref "U$16") (pin "4") (pinfunction "G_4") (pintype "input"))
    )
    (net (code "46") (name "Net-(U$16B-G)") (class "Default")
      (node (ref "R10") (pin "2") (pinfunction "2_2") (pintype "passive"))
      (node (ref "R14") (pin "1") (pinfunction "1_1") (pintype "passive"))
      (node (ref "U$16") (pin "2") (pinfunction "G_2") (pintype "input"))
    )
    (net (code "47") (name "Net-(U$36-3V3{slash}1)") (class "Default")
      (node (ref "J15") (pin "20") (pinfunction "20_20") (pintype "passive"))
      (node (ref "U$36") (pin "P$40") (pinfunction "3V3/1_P$40") (pintype "bidirectional"))
    )
    (net (code "48") (name "Net-(U$36-PA0{slash}A8)") (class "Default")
      (node (ref "J14") (pin "5") (pinfunction "5_5") (pintype "passive"))
      (node (ref "U$36") (pin "P$5") (pinfunction "PA0/A8_P$5") (pintype "bidirectional"))
    )
    (net (code "49") (name "Net-(U$36-PA6{slash}A2{slash}MISO1)") (class "Default")
      (node (ref "J14") (pin "11") (pinfunction "11_11") (pintype "passive"))
      (node (ref "U$36") (pin "P$11") (pinfunction "PA6/A2/MISO1_P$11") (pintype "bidirectional"))
    )
    (net (code "50") (name "Net-(U$36-PA11{slash}USB-)") (class "Default")
      (node (ref "J15") (pin "8") (pinfunction "8_8") (pintype "passive"))
      (node (ref "U$36") (pin "P$28") (pinfunction "PA11/USB-_P$28") (pintype "bidirectional"))
    )
    (net (code "51") (name "Net-(U$36-PA12{slash}USB+)") (class "Default")
      (node (ref "J15") (pin "9") (pinfunction "9_9") (pintype "passive"))
      (node (ref "U$36") (pin "P$29") (pinfunction "PA12/USB+_P$29") (pintype "bidirectional"))
    )
    (net (code "52") (name "Net-(U$36-PA15)") (class "Default")
      (node (ref "J15") (pin "10") (pinfunction "10_10") (pintype "passive"))
      (node (ref "U$36") (pin "P$30") (pinfunction "PA15_P$30") (pintype "bidirectional"))
    )
    (net (code "53") (name "Net-(U$36-PB3)") (class "Default")
      (node (ref "J15") (pin "11") (pinfunction "11_11") (pintype "passive"))
      (node (ref "U$36") (pin "P$31") (pinfunction "PB3_P$31") (pintype "bidirectional"))
    )
    (net (code "54") (name "Net-(U$36-PB4)") (class "Default")
      (node (ref "J15") (pin "12") (pinfunction "12_12") (pintype "passive"))
      (node (ref "U$36") (pin "P$32") (pinfunction "PB4_P$32") (pintype "bidirectional"))
    )
    (net (code "55") (name "Net-(U$36-PB5)") (class "Default")
      (node (ref "J15") (pin "13") (pinfunction "13_13") (pintype "passive"))
      (node (ref "U$36") (pin "P$33") (pinfunction "PB5_P$33") (pintype "bidirectional"))
    )
    (net (code "56") (name "Net-(U$36-PB9)") (class "Default")
      (node (ref "J15") (pin "17") (pinfunction "17_17") (pintype "passive"))
      (node (ref "U$36") (pin "P$37") (pinfunction "PB9_P$37") (pintype "bidirectional"))
    )
    (net (code "57") (name "Net-(U$36-PB10{slash}TX3{slash}SCL2)") (class "Default")
      (node (ref "J14") (pin "15") (pinfunction "15_15") (pintype "passive"))
      (node (ref "U$36") (pin "P$15") (pinfunction "PB10/TX3/SCL2_P$15") (pintype "bidirectional"))
    )
    (net (code "58") (name "Net-(U$36-PB11{slash}RX3{slash}SDA2)") (class "Default")
      (node (ref "J14") (pin "16") (pinfunction "16_16") (pintype "passive"))
      (node (ref "U$36") (pin "P$16") (pinfunction "PB11/RX3/SDA2_P$16") (pintype "bidirectional"))
    )
    (net (code "59") (name "Net-(U$36-PB12{slash}SS2)") (class "Default")
      (node (ref "J15") (pin "1") (pinfunction "1_1") (pintype "passive"))
      (node (ref "U$36") (pin "P$21") (pinfunction "PB12/SS2_P$21") (pintype "bidirectional"))
    )
    (net (code "60") (name "Net-(U$36-PB13{slash}SCK2)") (class "Default")
      (node (ref "J15") (pin "2") (pinfunction "2_2") (pintype "passive"))
      (node (ref "U$36") (pin "P$22") (pinfunction "PB13/SCK2_P$22") (pintype "bidirectional"))
    )
    (net (code "61") (name "Net-(U$36-PB14{slash}MIS02)") (class "Default")
      (node (ref "J15") (pin "3") (pinfunction "3_3") (pintype "passive"))
      (node (ref "U$36") (pin "P$23") (pinfunction "PB14/MIS02_P$23") (pintype "bidirectional"))
    )
    (net (code "62") (name "Net-(U$36-PB15{slash}MOSI2)") (class "Default")
      (node (ref "J15") (pin "4") (pinfunction "4_4") (pintype "passive"))
      (node (ref "U$36") (pin "P$24") (pinfunction "PB15/MOSI2_P$24") (pintype "bidirectional"))
    )
    (net (code "63") (name "Net-(U$36-PC13)") (class "Default")
      (node (ref "J14") (pin "2") (pinfunction "2_2") (pintype "passive"))
      (node (ref "U$36") (pin "P$2") (pinfunction "PC13_P$2") (pintype "bidirectional"))
    )
    (net (code "64") (name "Net-(U$36-PC14)") (class "Default")
      (node (ref "J14") (pin "3") (pinfunction "3_3") (pintype "passive"))
      (node (ref "U$36") (pin "P$3") (pinfunction "PC14_P$3") (pintype "bidirectional"))
    )
    (net (code "65") (name "Net-(U$36-PC15)") (class "Default")
      (node (ref "J14") (pin "4") (pinfunction "4_4") (pintype "passive"))
      (node (ref "U$36") (pin "P$4") (pinfunction "PC15_P$4") (pintype "bidirectional"))
    )
    (net (code "66") (name "Net-(U$36-RESET)") (class "Default")
      (node (ref "J14") (pin "17") (pinfunction "17_17") (pintype "passive"))
      (node (ref "U$36") (pin "P$17") (pinfunction "RESET_P$17") (pintype "bidirectional"))
    )
    (net (code "67") (name "Net-(U$36-VBAT)") (class "Default")
      (node (ref "J14") (pin "1") (pinfunction "1_1") (pintype "passive"))
      (node (ref "U$36") (pin "P$1") (pinfunction "VBAT_P$1") (pintype "bidirectional"))
    )
    (net (code "68") (name "unconnected-(IC3-GND-Pad2@1)") (class "Default")
      (node (ref "IC3") (pin "2@1") (pinfunction "GND_2@1") (pintype "passive"))
    )
    (net (code "69") (name "unconnected-(U$11-Pad1)") (class "Default")
      (node (ref "U$11") (pin "1") (pinfunction "1_1") (pintype "passive"))
    )
    (net (code "70") (name "unconnected-(U$11-Pad2)") (class "Default")
      (node (ref "U$11") (pin "2") (pinfunction "2_2") (pintype "passive"))
    )
    (net (code "71") (name "unconnected-(U$11-Pad3)") (class "Default")
      (node (ref "U$11") (pin "3") (pinfunction "3_3") (pintype "passive"))
    )
    (net (code "72") (name "unconnected-(U$11-Pad4)") (class "Default")
      (node (ref "U$11") (pin "4") (pinfunction "4_4") (pintype "passive"))
    )
    (net (code "73") (name "unconnected-(U$11-Pad5)") (class "Default")
      (node (ref "U$11") (pin "5") (pinfunction "5_5") (pintype "passive"))
    )
    (net (code "74") (name "unconnected-(U$11-Pad6)") (class "Default")
      (node (ref "U$11") (pin "6") (pinfunction "6_6") (pintype "passive"))
    )
    (net (code "75") (name "unconnected-(U$11-Pad7)") (class "Default")
      (node (ref "U$11") (pin "7") (pinfunction "7_7") (pintype "passive"))
    )
    (net (code "76") (name "unconnected-(U$11-Pad8)") (class "Default")
      (node (ref "U$11") (pin "8") (pinfunction "8_8") (pintype "passive"))
    )
    (net (code "77") (name "unconnected-(U$11-Pad9)") (class "Default")
      (node (ref "U$11") (pin "9") (pinfunction "9_9") (pintype "passive"))
    )
    (net (code "78") (name "unconnected-(U$11-Pad10)") (class "Default")
      (node (ref "U$11") (pin "10") (pinfunction "10_10") (pintype "passive"))
    )
    (net (code "79") (name "unconnected-(U$11-Pad11)") (class "Default")
      (node (ref "U$11") (pin "11") (pinfunction "11_11") (pintype "passive"))
    )
    (net (code "80") (name "unconnected-(U$11-Pad12)") (class "Default")
      (node (ref "U$11") (pin "12") (pinfunction "12_12") (pintype "passive"))
    )
    (net (code "81") (name "unconnected-(U$11-Pad13)") (class "Default")
      (node (ref "U$11") (pin "13") (pinfunction "13_13") (pintype "passive"))
    )
    (net (code "82") (name "unconnected-(U$11-Pad14)") (class "Default")
      (node (ref "U$11") (pin "14") (pinfunction "14_14") (pintype "passive"))
    )
    (net (code "83") (name "unconnected-(U$11-Pad15)") (class "Default")
      (node (ref "U$11") (pin "15") (pinfunction "15_15") (pintype "passive"))
    )
    (net (code "84") (name "unconnected-(U$11-Pad16)") (class "Default")
      (node (ref "U$11") (pin "16") (pinfunction "16_16") (pintype "passive"))
    )
    (net (code "85") (name "unconnected-(U$11-Pad17)") (class "Default")
      (node (ref "U$11") (pin "17") (pinfunction "17_17") (pintype "passive"))
    )
    (net (code "86") (name "unconnected-(U$11-Pad18)") (class "Default")
      (node (ref "U$11") (pin "18") (pinfunction "18_18") (pintype "passive"))
    )
    (net (code "87") (name "unconnected-(U$11-Pad19)") (class "Default")
      (node (ref "U$11") (pin "19") (pinfunction "19_19") (pintype "passive"))
    )
    (net (code "88") (name "unconnected-(U$11-Pad20)") (class "Default")
      (node (ref "U$11") (pin "20") (pinfunction "20_20") (pintype "passive"))
    )
    (net (code "89") (name "unconnected-(U$30-Pad1)") (class "Default")
      (node (ref "U$30") (pin "1") (pinfunction "1_1") (pintype "passive"))
    )
    (net (code "90") (name "unconnected-(U$30-Pad2)") (class "Default")
      (node (ref "U$30") (pin "2") (pinfunction "2_2") (pintype "passive"))
    )
    (net (code "91") (name "unconnected-(U$30-Pad3)") (class "Default")
      (node (ref "U$30") (pin "3") (pinfunction "3_3") (pintype "passive"))
    )
    (net (code "92") (name "unconnected-(U$30-Pad4)") (class "Default")
      (node (ref "U$30") (pin "4") (pinfunction "4_4") (pintype "passive"))
    )
    (net (code "93") (name "unconnected-(U$30-Pad7)") (class "Default")
      (node (ref "U$30") (pin "7") (pinfunction "7_7") (pintype "passive"))
    )
    (net (code "94") (name "unconnected-(U$30-Pad10)") (class "Default")
      (node (ref "U$30") (pin "10") (pinfunction "10_10") (pintype "passive"))
    )
    (net (code "95") (name "unconnected-(U$30-Pad17)") (class "Default")
      (node (ref "U$30") (pin "17") (pinfunction "17_17") (pintype "passive"))
    )
  )
)
